# 03-Actuators.net
KiCad netlist of a schematic drawn in Altium Designer
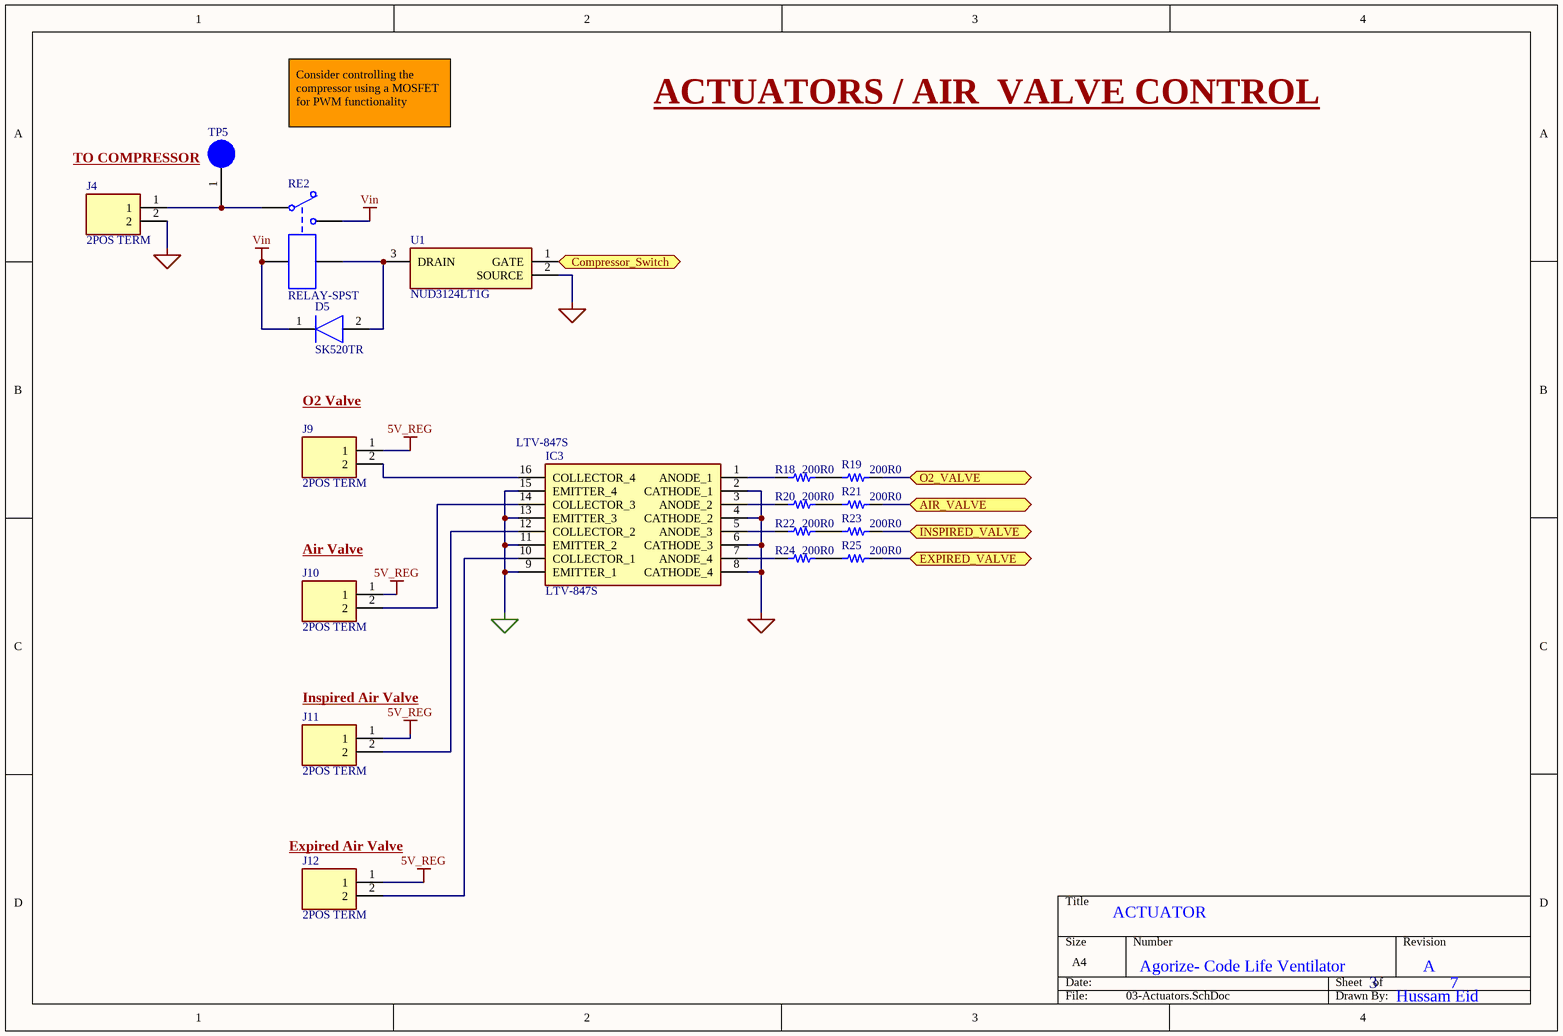
[diagram p0: 03-Actuators.SchDoc]

(export (version "E")
  (design (tool "Eeschema 10.0.6"))
  (components
    (comp (ref "D5")
      (value "SK520TR")
      (footprint "SamacSys:DIOM8060X295N")
      (description "DIODE SCHOTTKY 200V 5A SMC")
      (libsource (lib "*") (part "SK520TR"))
    )
    (comp (ref "IC3")
      (value "LTV-847S")
      (footprint "SamacSys:SOP254P1031X450-16N")
      (description "OPTOISOLTR 5KV 4CH TRANS 16-SMD")
      (fields (field (name "MANUFACTURER PART NUMBER 1") "LTV-847S"))
      (libsource (lib "*") (part "LTV-847S"))
    )
    (comp (ref "J4")
      (value "2POS TERM")
      (footprint "PcbLib1:SHDR2W110P0X500_1X2_1000X830X1140P")
      (description "TERM BLK 2POS SIDE ENTRY 5MM PCB")
      (fields (field (name "VOLTAGE") "300V"))
      (libsource (lib "*") (part "1935161"))
    )
    (comp (ref "J9")
      (value "2POS TERM")
      (footprint "PcbLib1:SHDR2W110P0X500_1X2_1000X830X1140P")
      (description "TERM BLK 2POS SIDE ENTRY 5MM PCB")
      (fields (field (name "VOLTAGE") "300V"))
      (libsource (lib "*") (part "1935161"))
    )
    (comp (ref "J10")
      (value "2POS TERM")
      (footprint "PcbLib1:SHDR2W110P0X500_1X2_1000X830X1140P")
      (description "TERM BLK 2POS SIDE ENTRY 5MM PCB")
      (fields (field (name "VOLTAGE") "300V"))
      (libsource (lib "*") (part "1935161"))
    )
    (comp (ref "J11")
      (value "2POS TERM")
      (footprint "PcbLib1:SHDR2W110P0X500_1X2_1000X830X1140P")
      (description "TERM BLK 2POS SIDE ENTRY 5MM PCB")
      (fields (field (name "VOLTAGE") "300V"))
      (libsource (lib "*") (part "1935161"))
    )
    (comp (ref "J12")
      (value "2POS TERM")
      (footprint "PcbLib1:SHDR2W110P0X500_1X2_1000X830X1140P")
      (description "TERM BLK 2POS SIDE ENTRY 5MM PCB")
      (fields (field (name "VOLTAGE") "300V"))
      (libsource (lib "*") (part "1935161"))
    )
    (comp (ref "R18")
      (value "200R0")
      (footprint "RES 1206/3216")
      (description "RES SMD 10K OHM 1% 1/4W 1206")
      (fields (field (name "TOLERANCE") "1%"))
      (libsource (lib "Celestial Library Database") (part "Resistor"))
    )
    (comp (ref "R19")
      (value "200R0")
      (footprint "RES 1206/3216")
      (description "RES SMD 10K OHM 1% 1/4W 1206")
      (fields (field (name "TOLERANCE") "1%"))
      (libsource (lib "Celestial Library Database") (part "Resistor"))
    )
    (comp (ref "R20")
      (value "200R0")
      (footprint "RES 1206/3216")
      (description "RES SMD 10K OHM 1% 1/4W 1206")
      (fields (field (name "TOLERANCE") "1%"))
      (libsource (lib "Celestial Library Database") (part "Resistor"))
    )
    (comp (ref "R21")
      (value "200R0")
      (footprint "RES 1206/3216")
      (description "RES SMD 10K OHM 1% 1/4W 1206")
      (fields (field (name "TOLERANCE") "1%"))
      (libsource (lib "Celestial Library Database") (part "Resistor"))
    )
    (comp (ref "R22")
      (value "200R0")
      (footprint "RES 1206/3216")
      (description "RES SMD 10K OHM 1% 1/4W 1206")
      (fields (field (name "TOLERANCE") "1%"))
      (libsource (lib "Celestial Library Database") (part "Resistor"))
    )
    (comp (ref "R23")
      (value "200R0")
      (footprint "RES 1206/3216")
      (description "RES SMD 10K OHM 1% 1/4W 1206")
      (fields (field (name "TOLERANCE") "1%"))
      (libsource (lib "Celestial Library Database") (part "Resistor"))
    )
    (comp (ref "R24")
      (value "200R0")
      (footprint "RES 1206/3216")
      (description "RES SMD 10K OHM 1% 1/4W 1206")
      (fields (field (name "TOLERANCE") "1%"))
      (libsource (lib "Celestial Library Database") (part "Resistor"))
    )
    (comp (ref "R25")
      (value "200R0")
      (footprint "RES 1206/3216")
      (description "RES SMD 10K OHM 1% 1/4W 1206")
      (fields (field (name "TOLERANCE") "1%"))
      (libsource (lib "Celestial Library Database") (part "Resistor"))
    )
    (comp (ref "RE2")
      (value "RELAY-SPST")
      (footprint "JSM1A12V4")
      (description "RELAY AUTOMOTIVE SPST 15A 12V")
      (libsource (lib "Schlib1") (part "RELAY-SPST"))
    )
    (comp (ref "TP5")
      (value "TP")
      (footprint "TP")
      (description "Test Point")
      (libsource (lib "Schlib1") (part "TP"))
    )
    (comp (ref "U1")
      (value "NUD3124LT1G")
      (footprint "SamacSys:SOT96P237X111-3N")
      (description "IC PWR DRVR N-CHAN 1:1 SOT23-3")
      (libsource (lib "*") (part "NUD3124LT1G"))
    )
  )
  (nets
    (net (code "1") (name "/AIR_VALVE") (class "Default")
      (node (ref "R21") (pin "1") (pinfunction "1_1") (pintype "passive"))
    )
    (net (code "2") (name "/Compressor_Switch") (class "Default")
      (node (ref "U1") (pin "1") (pinfunction "GATE_1") (pintype "passive"))
    )
    (net (code "3") (name "/EXPIRED_VALVE") (class "Default")
      (node (ref "R25") (pin "1") (pinfunction "1_1") (pintype "passive"))
    )
    (net (code "4") (name "/INSPIRED_VALVE") (class "Default")
      (node (ref "R23") (pin "1") (pinfunction "1_1") (pintype "passive"))
    )
    (net (code "5") (name "/O2_VALVE") (class "Default")
      (node (ref "R19") (pin "1") (pinfunction "1_1") (pintype "passive"))
    )
    (net (code "6") (name "5V_REG") (class "Default")
      (node (ref "J10") (pin "1") (pinfunction "1_1") (pintype "passive"))
      (node (ref "J11") (pin "1") (pinfunction "1_1") (pintype "passive"))
      (node (ref "J12") (pin "1") (pinfunction "1_1") (pintype "passive"))
      (node (ref "J9") (pin "1") (pinfunction "1_1") (pintype "passive"))
    )
    (net (code "7") (name "COM") (class "Default")
      (node (ref "IC3") (pin "2") (pinfunction "CATHODE_1_2") (pintype "passive"))
      (node (ref "IC3") (pin "4") (pinfunction "CATHODE_2_4") (pintype "passive"))
      (node (ref "IC3") (pin "6") (pinfunction "CATHODE_3_6") (pintype "passive"))
      (node (ref "IC3") (pin "8") (pinfunction "CATHODE_4_8") (pintype "passive"))
      (node (ref "J4") (pin "2") (pinfunction "2_2") (pintype "passive"))
      (node (ref "U1") (pin "2") (pinfunction "SOURCE_2") (pintype "passive"))
    )
    (net (code "8") (name "COM_ISO") (class "Default")
      (node (ref "IC3") (pin "11") (pinfunction "EMITTER_2_11") (pintype "passive"))
      (node (ref "IC3") (pin "13") (pinfunction "EMITTER_3_13") (pintype "passive"))
      (node (ref "IC3") (pin "15") (pinfunction "EMITTER_4_15") (pintype "passive"))
      (node (ref "IC3") (pin "9") (pinfunction "EMITTER_1_9") (pintype "passive"))
    )
    (net (code "9") (name "Net-(D5-A)") (class "Default")
      (node (ref "D5") (pin "2") (pinfunction "A_2") (pintype "passive"))
      (node (ref "RE2") (pin "5") (pinfunction "5_5") (pintype "passive"))
      (node (ref "U1") (pin "3") (pinfunction "DRAIN_3") (pintype "passive"))
    )
    (net (code "10") (name "Net-(IC3-ANODE_1)") (class "Default")
      (node (ref "IC3") (pin "1") (pinfunction "ANODE_1_1") (pintype "passive"))
      (node (ref "R18") (pin "2") (pinfunction "2_2") (pintype "passive"))
    )
    (net (code "11") (name "Net-(IC3-ANODE_2)") (class "Default")
      (node (ref "IC3") (pin "3") (pinfunction "ANODE_2_3") (pintype "passive"))
      (node (ref "R20") (pin "2") (pinfunction "2_2") (pintype "passive"))
    )
    (net (code "12") (name "Net-(IC3-ANODE_3)") (class "Default")
      (node (ref "IC3") (pin "5") (pinfunction "ANODE_3_5") (pintype "passive"))
      (node (ref "R22") (pin "2") (pinfunction "2_2") (pintype "passive"))
    )
    (net (code "13") (name "Net-(IC3-ANODE_4)") (class "Default")
      (node (ref "IC3") (pin "7") (pinfunction "ANODE_4_7") (pintype "passive"))
      (node (ref "R24") (pin "2") (pinfunction "2_2") (pintype "passive"))
    )
    (net (code "14") (name "Net-(IC3-COLLECTOR_1)") (class "Default")
      (node (ref "IC3") (pin "10") (pinfunction "COLLECTOR_1_10") (pintype "passive"))
      (node (ref "J12") (pin "2") (pinfunction "2_2") (pintype "passive"))
    )
    (net (code "15") (name "Net-(IC3-COLLECTOR_2)") (class "Default")
      (node (ref "IC3") (pin "12") (pinfunction "COLLECTOR_2_12") (pintype "passive"))
      (node (ref "J11") (pin "2") (pinfunction "2_2") (pintype "passive"))
    )
    (net (code "16") (name "Net-(IC3-COLLECTOR_3)") (class "Default")
      (node (ref "IC3") (pin "14") (pinfunction "COLLECTOR_3_14") (pintype "passive"))
      (node (ref "J10") (pin "2") (pinfunction "2_2") (pintype "passive"))
    )
    (net (code "17") (name "Net-(IC3-COLLECTOR_4)") (class "Default")
      (node (ref "IC3") (pin "16") (pinfunction "COLLECTOR_4_16") (pintype "passive"))
      (node (ref "J9") (pin "2") (pinfunction "2_2") (pintype "passive"))
    )
    (net (code "18") (name "Net-(J4-Pad1)") (class "Default")
      (node (ref "J4") (pin "1") (pinfunction "1_1") (pintype "passive"))
      (node (ref "RE2") (pin "1") (pinfunction "1_1") (pintype "passive"))
      (node (ref "TP5") (pin "1") (pinfunction "1_1") (pintype "passive"))
    )
    (net (code "19") (name "Net-(R18-Pad1)") (class "Default")
      (node (ref "R18") (pin "1") (pinfunction "1_1") (pintype "passive"))
      (node (ref "R19") (pin "2") (pinfunction "2_2") (pintype "passive"))
    )
    (net (code "20") (name "Net-(R20-Pad1)") (class "Default")
      (node (ref "R20") (pin "1") (pinfunction "1_1") (pintype "passive"))
      (node (ref "R21") (pin "2") (pinfunction "2_2") (pintype "passive"))
    )
    (net (code "21") (name "Net-(R22-Pad1)") (class "Default")
      (node (ref "R22") (pin "1") (pinfunction "1_1") (pintype "passive"))
      (node (ref "R23") (pin "2") (pinfunction "2_2") (pintype "passive"))
    )
    (net (code "22") (name "Net-(R24-Pad1)") (class "Default")
      (node (ref "R24") (pin "1") (pinfunction "1_1") (pintype "passive"))
      (node (ref "R25") (pin "2") (pinfunction "2_2") (pintype "passive"))
    )
    (net (code "23") (name "Vin") (class "Default")
      (node (ref "D5") (pin "1") (pinfunction "K_1") (pintype "passive"))
      (node (ref "RE2") (pin "2") (pinfunction "2_2") (pintype "passive"))
      (node (ref "RE2") (pin "3") (pinfunction "3_3") (pintype "passive"))
    )
  )
)
